# SoilMoistureMan.net
KiCad netlist of a schematic drawn in EAGLE
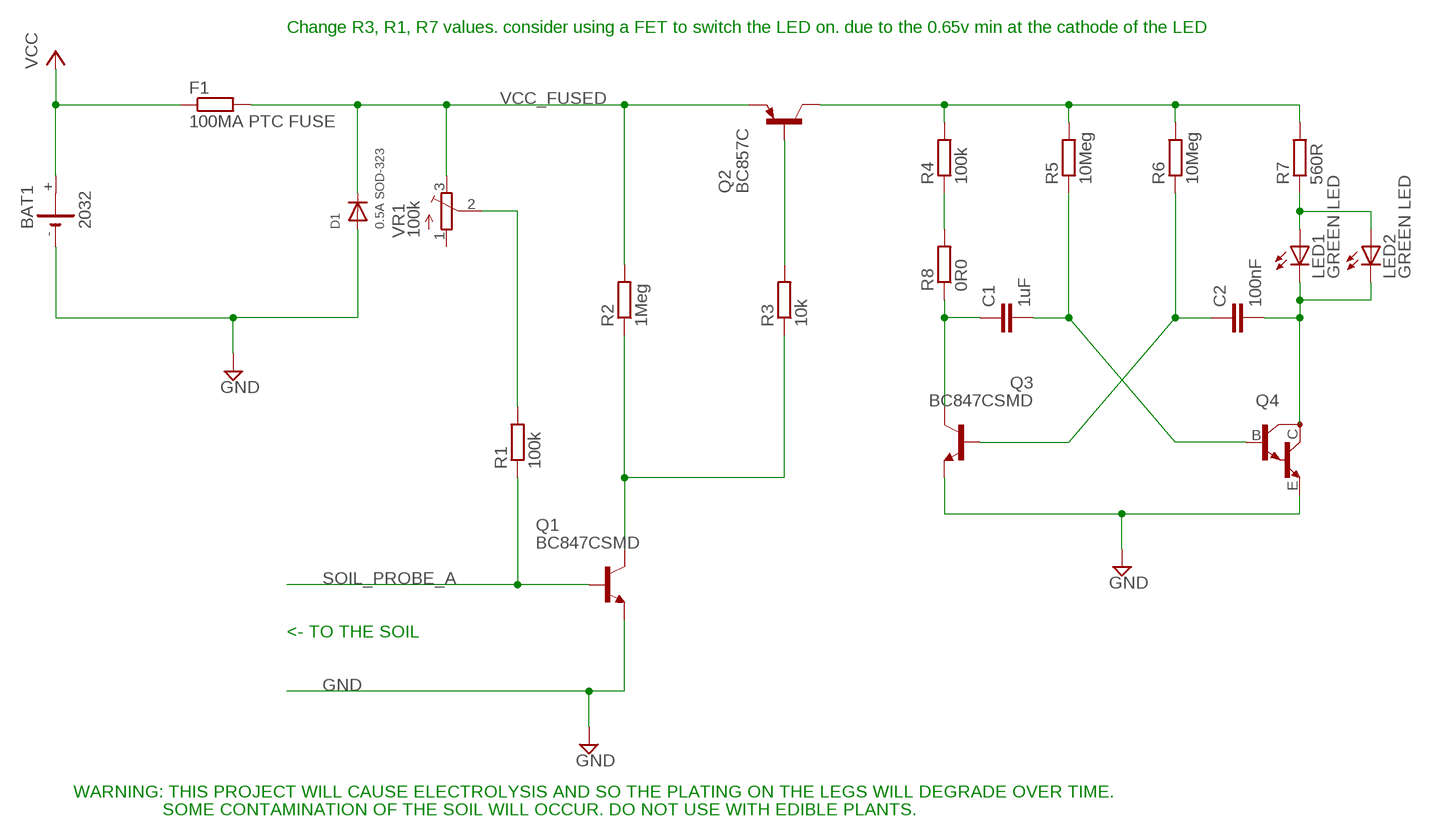
[diagram p0: schematic, sheet 1]

(export (version "E")
  (design (tool "Eeschema 10.0.6"))
  (components
    (comp (ref "BAT1")
      (value "2032")
      (footprint "eagle-import:KZH20SMD")
      (fields (field (name "MF") "RENATA") (field (name "MPN") "SMTU 2032-LF"))
      (libsource (lib "eagle-import") (part "2032"))
    )
    (comp (ref "C1")
      (value "1uF")
      (footprint "eagle-import:C0603")
      (fields (field (name "MF") "TDK") (field (name "MPN") "C1608X5R1C105K080AA"))
      (libsource (lib "eagle-import") (part "C-EUC0603"))
    )
    (comp (ref "C2")
      (value "100nF")
      (footprint "eagle-import:C0603")
      (fields (field (name "MF") "MULTICOMP") (field (name "MPN") "MC0603B104K160CT"))
      (libsource (lib "eagle-import") (part "C-EUC0603"))
    )
    (comp (ref "D1")
      (value "0.5A SOD-323")
      (footprint "eagle-import:SOD-323F")
      (fields (field (name "MF") "NXP") (field (name "MPN") "PMEG3010EJ,115"))
      (libsource (lib "eagle-import") (part "DIODESOD-323F"))
    )
    (comp (ref "F1")
      (value "100MA PTC FUSE")
      (footprint "eagle-import:R0805")
      (fields (field (name "MF") "BOURNS") (field (name "MPN") "MF-PSMF010X-2"))
      (libsource (lib "eagle-import") (part "R-EU_R0805"))
    )
    (comp (ref "LED1")
      (value "GREEN LED")
      (footprint "eagle-import:P-LCC-2")
      (fields (field (name "MF") "OSRAM") (field (name "MPN") "LGT67K-H2K1-24-Z"))
      (libsource (lib "eagle-import") (part "LEDP-LCC-2"))
    )
    (comp (ref "LED2")
      (value "GREEN LED")
      (footprint "eagle-import:P-LCC-2")
      (fields (field (name "MF") "OSRAM") (field (name "MPN") "LGT67K-H2K1-24-Z"))
      (libsource (lib "eagle-import") (part "LEDP-LCC-2"))
    )
    (comp (ref "Q1")
      (value "BC847CSMD")
      (footprint "eagle-import:SOT23")
      (fields (field (name "MF") "DIODES INC.") (field (name "MPN") "BC847C-7-F"))
      (libsource (lib "eagle-import") (part "BC847SMDC"))
    )
    (comp (ref "Q2")
      (value "BC857C")
      (footprint "eagle-import:SOT23-BEC")
      (fields (field (name "MF") "DIODES INC.") (field (name "MPN") "BC857C-7-F"))
      (libsource (lib "eagle-import") (part "-PNP-SOT23-BECBC857C"))
    )
    (comp (ref "Q3")
      (value "BC847CSMD")
      (footprint "eagle-import:SOT23")
      (fields (field (name "MF") "DIODES INC.") (field (name "MPN") "BC847C-7-F"))
      (libsource (lib "eagle-import") (part "BC847SMDC"))
    )
    (comp (ref "Q4")
      (value "MMBTA13LT1")
      (footprint "eagle-import:SOT23-BEC")
      (fields (field (name "MF") "FAIRCHILD SEMICONDUCTOR") (field (name "MPN") "BCV27"))
      (libsource (lib "eagle-import") (part "MMBTA13LT1"))
    )
    (comp (ref "R1")
      (value "100k")
      (footprint "eagle-import:R0603")
      (fields (field (name "MF") "TE CONNECTIVITY") (field (name "MPN") "CRGH0603J100K"))
      (libsource (lib "eagle-import") (part "resistor_R-EU_R0603"))
    )
    (comp (ref "R2")
      (value "1Meg")
      (footprint "eagle-import:R0603")
      (fields (field (name "MF") "TE CONNECTIVITY") (field (name "MPN") "CRGH0603J1M0"))
      (libsource (lib "eagle-import") (part "resistor_R-EU_R0603"))
    )
    (comp (ref "R3")
      (value "10k")
      (footprint "eagle-import:R0603")
      (fields (field (name "MF") "BOURNS") (field (name "MPN") "CR0603-JW-103GLF"))
      (libsource (lib "eagle-import") (part "resistor_R-EU_R0603"))
    )
    (comp (ref "R4")
      (value "100k")
      (footprint "eagle-import:R0603")
      (fields (field (name "MF") "TE CONNECTIVITY") (field (name "MPN") "CRGH0603J100K"))
      (libsource (lib "eagle-import") (part "resistor_R-EU_R0603"))
    )
    (comp (ref "R5")
      (value "10Meg")
      (footprint "eagle-import:R0603")
      (fields (field (name "MF") "MULTICOMP") (field (name "MPN") "MC0063W0603110M0"))
      (libsource (lib "eagle-import") (part "resistor_R-EU_R0603"))
    )
    (comp (ref "R6")
      (value "10Meg")
      (footprint "eagle-import:R0603")
      (fields (field (name "MF") "MULTICOMP") (field (name "MPN") "MC0063W0603110M0"))
      (libsource (lib "eagle-import") (part "resistor_R-EU_R0603"))
    )
    (comp (ref "R7")
      (value "560R")
      (footprint "eagle-import:R0603")
      (fields (field (name "MF") "TE CONNECTIVITY") (field (name "MPN") "CRGH0603J560R"))
      (libsource (lib "eagle-import") (part "resistor_R-EU_R0603"))
    )
    (comp (ref "R8")
      (value "0R0")
      (footprint "eagle-import:R0603")
      (fields (field (name "MF") "MULTICOMP") (field (name "MPN") "MC0603SAF0000T5E"))
      (libsource (lib "eagle-import") (part "resistor_R-EU_R0603"))
    )
    (comp (ref "VR1")
      (value "100k")
      (footprint "eagle-import:TC33X")
      (fields (field (name "MF") "VISHAY SFERNICE") (field (name "MPN") "TS53YJ104MR10"))
      (libsource (lib "eagle-import") (part "TRIMPOTTC33X"))
    )
  )
  (nets
    (net (code "1") (name "/SOIL_PROBE_A") (class "Default")
      (node (ref "Q1") (pin "1") (pinfunction "B_1") (pintype "passive"))
      (node (ref "R1") (pin "1") (pinfunction "1_1") (pintype "passive"))
    )
    (net (code "2") (name "/VCC_FUSED") (class "Default")
      (node (ref "D1") (pin "C") (pinfunction "C_C") (pintype "passive"))
      (node (ref "F1") (pin "2") (pinfunction "2_2") (pintype "passive"))
      (node (ref "Q2") (pin "E") (pinfunction "E_E") (pintype "passive"))
      (node (ref "R2") (pin "2") (pinfunction "2_2") (pintype "passive"))
      (node (ref "VR1") (pin "3") (pinfunction "E_3") (pintype "passive"))
    )
    (net (code "3") (name "GND") (class "Default")
      (node (ref "BAT1") (pin "-") (pinfunction "-_-") (pintype "passive"))
      (node (ref "D1") (pin "A") (pinfunction "A_A") (pintype "passive"))
      (node (ref "Q1") (pin "2") (pinfunction "E_2") (pintype "passive"))
      (node (ref "Q3") (pin "2") (pinfunction "E_2") (pintype "passive"))
      (node (ref "Q4") (pin "E") (pinfunction "E_E") (pintype "passive"))
    )
    (net (code "4") (name "Net-(C1-Pad2)") (class "Default")
      (node (ref "C1") (pin "2") (pinfunction "2_2") (pintype "passive"))
      (node (ref "Q4") (pin "B") (pinfunction "B_B") (pintype "passive"))
      (node (ref "R5") (pin "1") (pinfunction "1_1") (pintype "passive"))
    )
    (net (code "5") (name "Net-(C2-Pad2)") (class "Default")
      (node (ref "C2") (pin "2") (pinfunction "2_2") (pintype "passive"))
      (node (ref "LED1") (pin "C") (pinfunction "C_C") (pintype "passive"))
      (node (ref "LED2") (pin "C") (pinfunction "C_C") (pintype "passive"))
      (node (ref "Q4") (pin "C") (pinfunction "C_C") (pintype "passive"))
    )
    (net (code "6") (name "Net-(LED1-PadA)") (class "Default")
      (node (ref "LED1") (pin "A") (pinfunction "A_A") (pintype "passive"))
      (node (ref "LED2") (pin "A") (pinfunction "A_A") (pintype "passive"))
      (node (ref "R7") (pin "1") (pinfunction "1_1") (pintype "passive"))
    )
    (net (code "7") (name "Net-(Q1-C)") (class "Default")
      (node (ref "Q1") (pin "3") (pinfunction "C_3") (pintype "passive"))
      (node (ref "R2") (pin "1") (pinfunction "1_1") (pintype "passive"))
      (node (ref "R3") (pin "1") (pinfunction "1_1") (pintype "passive"))
    )
    (net (code "8") (name "Net-(Q2-PadB)") (class "Default")
      (node (ref "Q2") (pin "B") (pinfunction "B_B") (pintype "passive"))
      (node (ref "R3") (pin "2") (pinfunction "2_2") (pintype "passive"))
    )
    (net (code "9") (name "Net-(Q2-PadC)") (class "Default")
      (node (ref "Q2") (pin "C") (pinfunction "C_C") (pintype "passive"))
      (node (ref "R4") (pin "2") (pinfunction "2_2") (pintype "passive"))
      (node (ref "R5") (pin "2") (pinfunction "2_2") (pintype "passive"))
      (node (ref "R6") (pin "2") (pinfunction "2_2") (pintype "passive"))
      (node (ref "R7") (pin "2") (pinfunction "2_2") (pintype "passive"))
    )
    (net (code "10") (name "Net-(Q3-B)") (class "Default")
      (node (ref "C2") (pin "1") (pinfunction "1_1") (pintype "passive"))
      (node (ref "Q3") (pin "1") (pinfunction "B_1") (pintype "passive"))
      (node (ref "R6") (pin "1") (pinfunction "1_1") (pintype "passive"))
    )
    (net (code "11") (name "Net-(Q3-C)") (class "Default")
      (node (ref "C1") (pin "1") (pinfunction "1_1") (pintype "passive"))
      (node (ref "Q3") (pin "3") (pinfunction "C_3") (pintype "passive"))
      (node (ref "R8") (pin "1") (pinfunction "1_1") (pintype "passive"))
    )
    (net (code "12") (name "Net-(R4-Pad1)") (class "Default")
      (node (ref "R4") (pin "1") (pinfunction "1_1") (pintype "passive"))
      (node (ref "R8") (pin "2") (pinfunction "2_2") (pintype "passive"))
    )
    (net (code "13") (name "Net-(VR1-S)") (class "Default")
      (node (ref "R1") (pin "2") (pinfunction "2_2") (pintype "passive"))
      (node (ref "VR1") (pin "2") (pinfunction "S_2") (pintype "passive"))
    )
    (net (code "14") (name "VCC") (class "Default")
      (node (ref "BAT1") (pin "+") (pinfunction "+_+") (pintype "passive"))
      (node (ref "F1") (pin "1") (pinfunction "1_1") (pintype "passive"))
    )
    (net (code "15") (name "unconnected-(VR1-A-Pad1)") (class "Default")
      (node (ref "VR1") (pin "1") (pinfunction "A_1") (pintype "passive"))
    )
  )
)
